# SolarPanel.net
KiCad netlist of a schematic drawn in Altium Designer
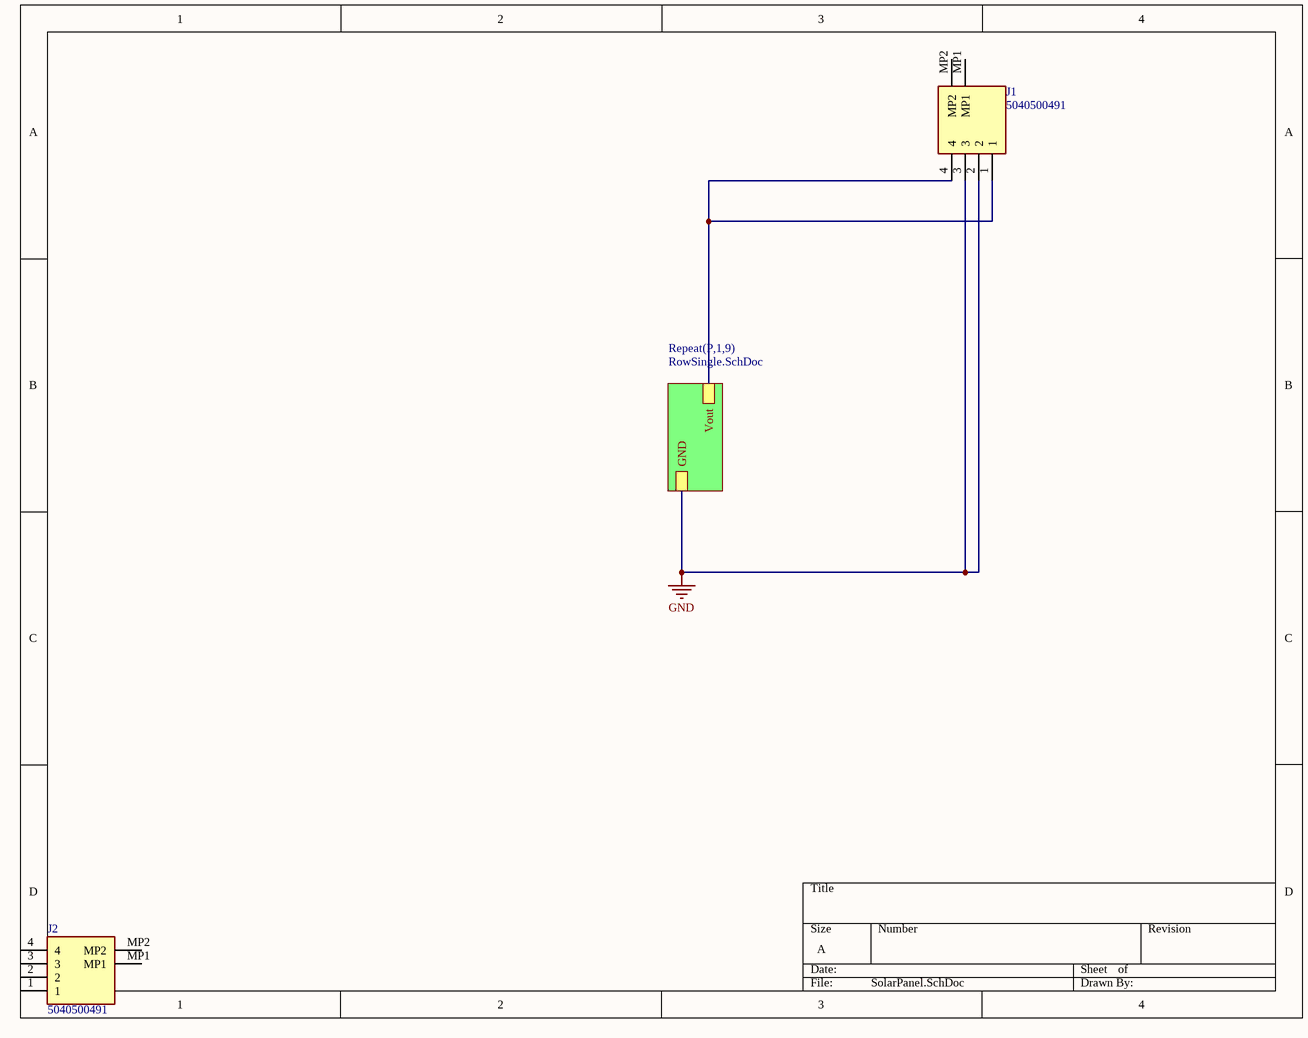
[diagram p0: SolarPanel.SchDoc]

(export (version "E")
  (design (tool "Eeschema 10.0.6"))
  (components
    (comp (ref "J1")
      (value "5040500491")
      (footprint "SamacSys:5040500491")
      (description "Connector")
      (libsource (lib "SamacSys") (part "5040500491"))
    )
    (comp (ref "J2")
      (value "5040500491")
      (footprint "SamacSys:5040500491")
      (description "Connector")
      (libsource (lib "*") (part "5040500491"))
    )
  )
  (nets
    (net (code "1") (name "/Vout") (class "Default")
      (node (ref "J1") (pin "1") (pinfunction "1_1") (pintype "passive"))
      (node (ref "J1") (pin "4") (pinfunction "4_4") (pintype "passive"))
    )
    (net (code "2") (name "GND") (class "Default")
      (node (ref "J1") (pin "2") (pinfunction "2_2") (pintype "passive"))
      (node (ref "J1") (pin "3") (pinfunction "3_3") (pintype "passive"))
    )
    (net (code "3") (name "unconnected-(J1-PadMP1)") (class "Default")
      (node (ref "J1") (pin "MP1") (pinfunction "MP1_MP1") (pintype "passive"))
    )
    (net (code "4") (name "unconnected-(J1-PadMP2)") (class "Default")
      (node (ref "J1") (pin "MP2") (pinfunction "MP2_MP2") (pintype "passive"))
    )
    (net (code "5") (name "unconnected-(J2-Pad1)") (class "Default")
      (node (ref "J2") (pin "1") (pinfunction "1_1") (pintype "passive"))
    )
    (net (code "6") (name "unconnected-(J2-Pad2)") (class "Default")
      (node (ref "J2") (pin "2") (pinfunction "2_2") (pintype "passive"))
    )
    (net (code "7") (name "unconnected-(J2-Pad3)") (class "Default")
      (node (ref "J2") (pin "3") (pinfunction "3_3") (pintype "passive"))
    )
    (net (code "8") (name "unconnected-(J2-Pad4)") (class "Default")
      (node (ref "J2") (pin "4") (pinfunction "4_4") (pintype "passive"))
    )
    (net (code "9") (name "unconnected-(J2-PadMP1)") (class "Default")
      (node (ref "J2") (pin "MP1") (pinfunction "MP1_MP1") (pintype "passive"))
    )
    (net (code "10") (name "unconnected-(J2-PadMP2)") (class "Default")
      (node (ref "J2") (pin "MP2") (pinfunction "MP2_MP2") (pintype "passive"))
    )
  )
)
